# lvc.net
KiCad netlist of a schematic drawn in EAGLE
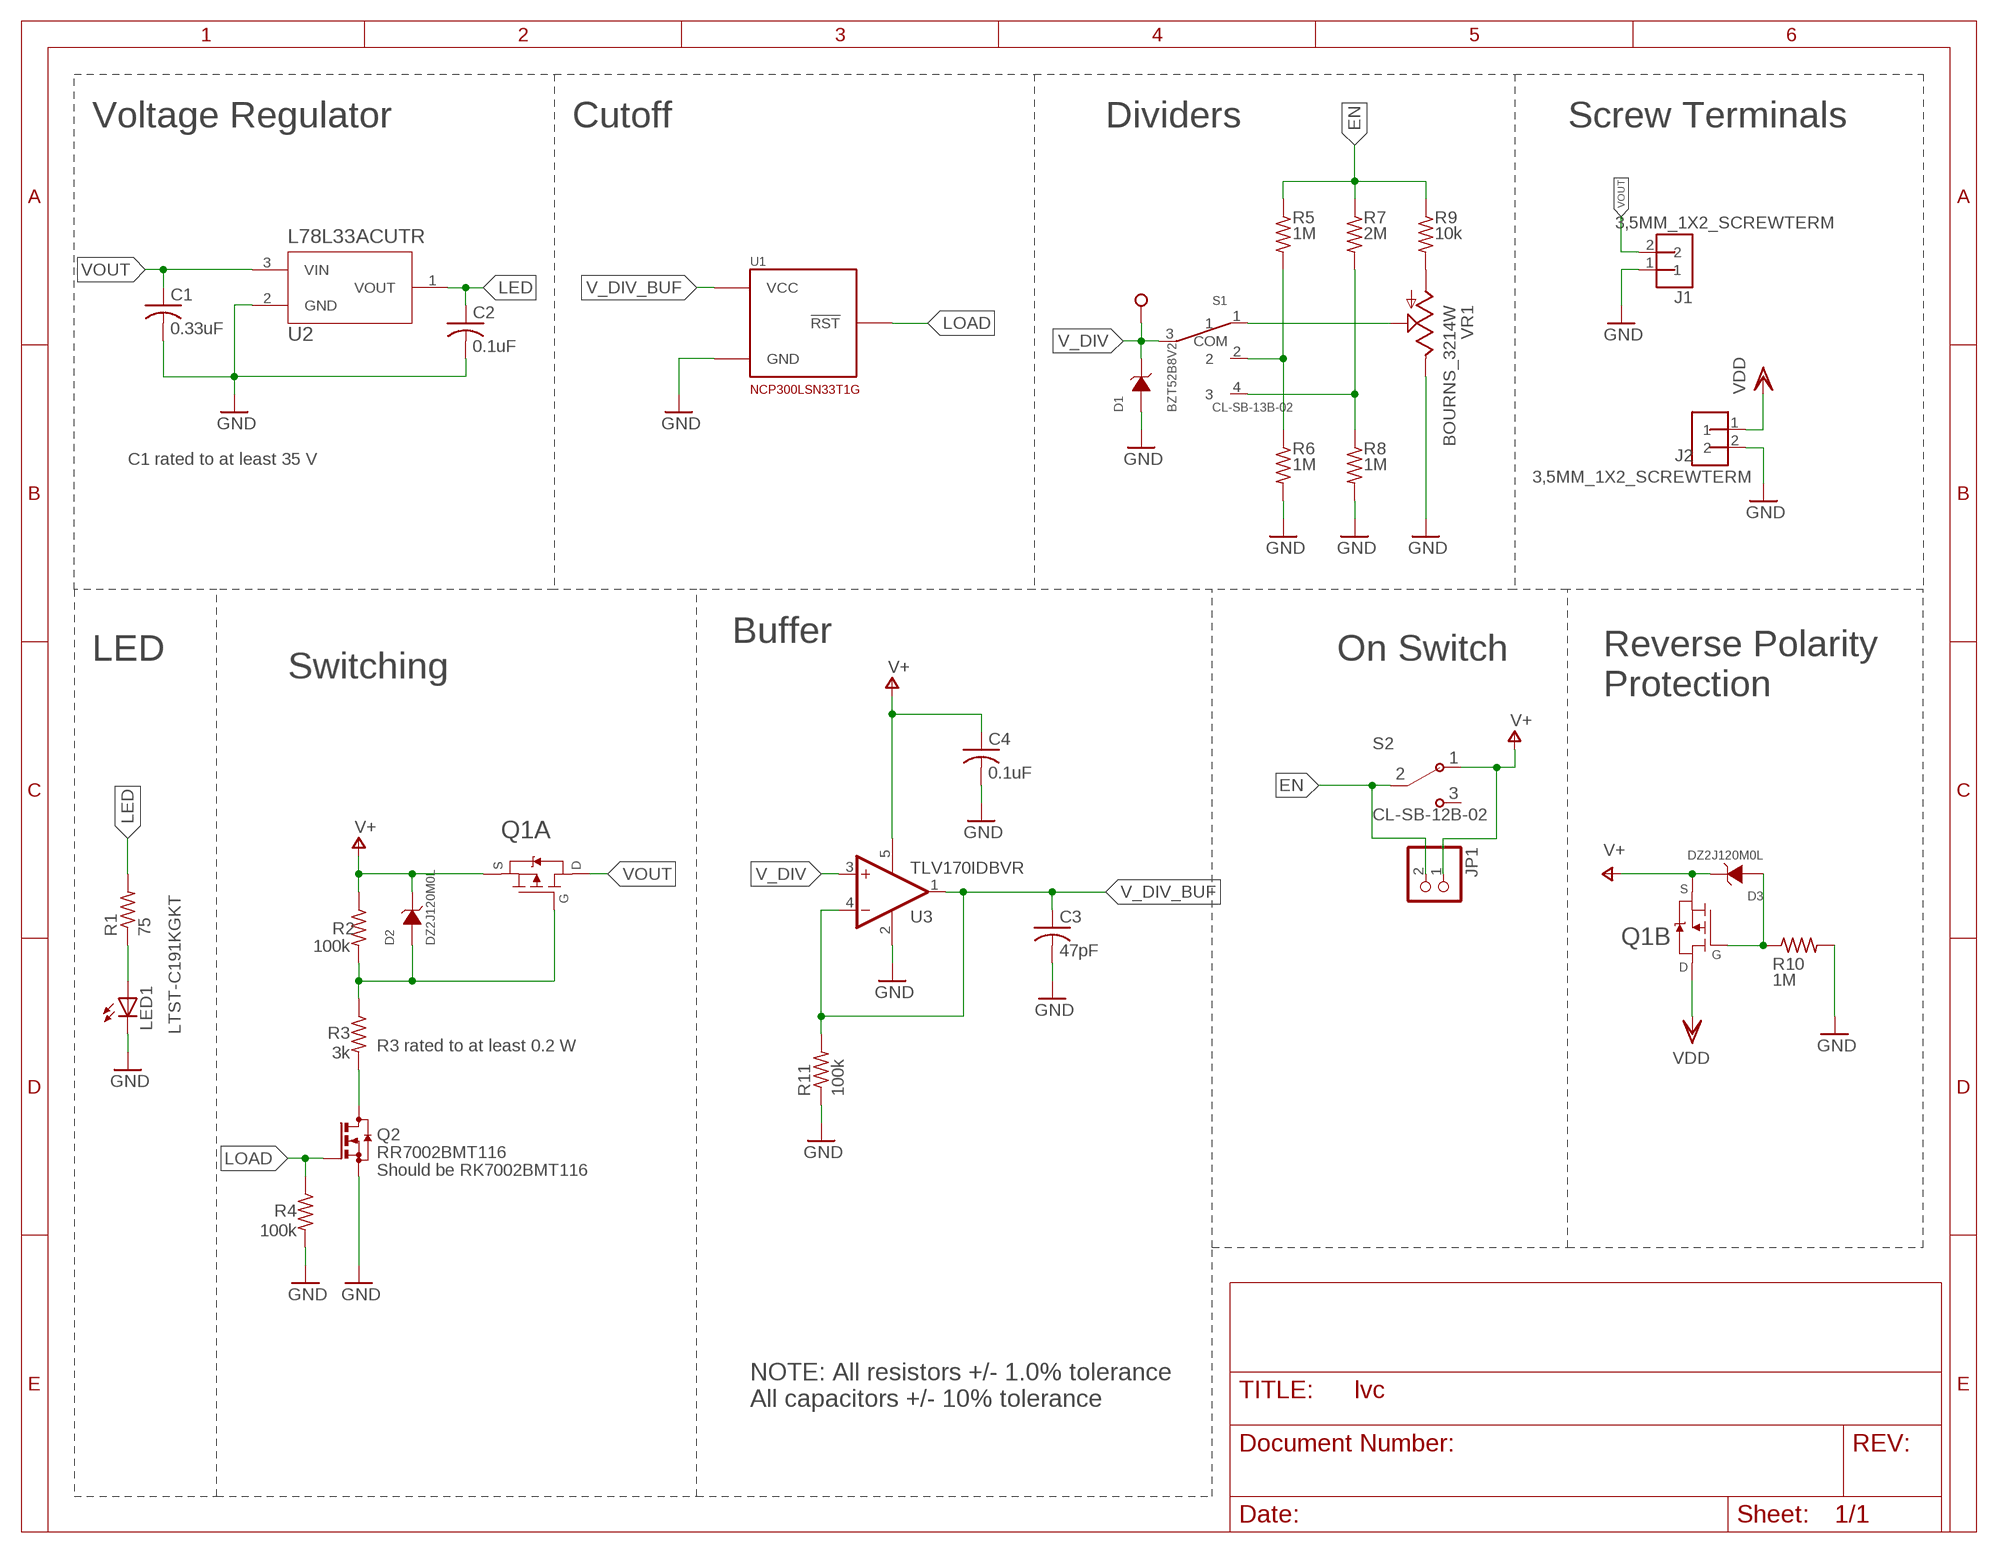
[diagram p0: schematic, sheet 1]

(export (version "E")
  (design (tool "Eeschema 10.0.6"))
  (components
    (comp (ref "C1")
      (value "0.33uF")
      (footprint "eagle-import:C0603")
      (libsource (lib "eagle-import") (part "C-USC0603"))
    )
    (comp (ref "C2")
      (value "0.1uF")
      (footprint "eagle-import:C0603")
      (libsource (lib "eagle-import") (part "C-USC0603"))
    )
    (comp (ref "C3")
      (value "47pF")
      (footprint "eagle-import:C0603")
      (libsource (lib "eagle-import") (part "C-USC0603"))
    )
    (comp (ref "C4")
      (value "0.1uF")
      (footprint "eagle-import:C0603")
      (libsource (lib "eagle-import") (part "C-USC0603"))
    )
    (comp (ref "D1")
      (value "BZT52B8V2")
      (footprint "eagle-import:SOD123")
      (libsource (lib "eagle-import") (part "BZT52B8V2"))
    )
    (comp (ref "D2")
      (value "DZ2J120M0L")
      (footprint "eagle-import:SMINI2-F5-B")
      (libsource (lib "eagle-import") (part "DZ2J120M0L"))
    )
    (comp (ref "D3")
      (value "DZ2J120M0L")
      (footprint "eagle-import:SMINI2-F5-B")
      (libsource (lib "eagle-import") (part "DZ2J120M0L"))
    )
    (comp (ref "J1")
      (value "3,5MM_1X2_SCREWTERM")
      (footprint "eagle-import:3.5MM_1X2")
      (libsource (lib "eagle-import") (part "3,5MM_1X2_SCREWTERM"))
    )
    (comp (ref "J2")
      (value "3,5MM_1X2_SCREWTERM")
      (footprint "eagle-import:3.5MM_1X2")
      (libsource (lib "eagle-import") (part "3,5MM_1X2_SCREWTERM"))
    )
    (comp (ref "JP1")
      (value "PINHD-1X2")
      (footprint "eagle-import:1X02")
      (libsource (lib "eagle-import") (part "PINHD-1X2"))
    )
    (comp (ref "LED1")
      (value "LEDCHIPLED_0603")
      (footprint "eagle-import:CHIPLED_0603")
      (libsource (lib "eagle-import") (part "LEDCHIPLED_0603"))
    )
    (comp (ref "Q1")
      (value "SI7997DP")
      (footprint "eagle-import:POWERPAK-SO-8-DUAL")
      (libsource (lib "eagle-import") (part "SI7997DP"))
    )
    (comp (ref "Q2")
      (value "RR7002BMT116")
      (footprint "eagle-import:SOT23")
      (libsource (lib "eagle-import") (part "RR7002BMT116"))
    )
    (comp (ref "R1")
      (value "75")
      (footprint "eagle-import:R0603")
      (libsource (lib "eagle-import") (part "R-US_R0603"))
    )
    (comp (ref "R2")
      (value "100k")
      (footprint "eagle-import:R0603")
      (libsource (lib "eagle-import") (part "resistor_348_R-US_R0603"))
    )
    (comp (ref "R3")
      (value "3k")
      (footprint "eagle-import:R0603")
      (libsource (lib "eagle-import") (part "resistor_348_R-US_R0603"))
    )
    (comp (ref "R4")
      (value "100k")
      (footprint "eagle-import:R0603")
      (libsource (lib "eagle-import") (part "resistor_348_R-US_R0603"))
    )
    (comp (ref "R5")
      (value "1M")
      (footprint "eagle-import:R0603")
      (libsource (lib "eagle-import") (part "resistor_348_R-US_R0603"))
    )
    (comp (ref "R6")
      (value "1M")
      (footprint "eagle-import:R0603")
      (libsource (lib "eagle-import") (part "resistor_348_R-US_R0603"))
    )
    (comp (ref "R7")
      (value "2M")
      (footprint "eagle-import:R0603")
      (libsource (lib "eagle-import") (part "resistor_348_R-US_R0603"))
    )
    (comp (ref "R8")
      (value "1M")
      (footprint "eagle-import:R0603")
      (libsource (lib "eagle-import") (part "resistor_348_R-US_R0603"))
    )
    (comp (ref "R9")
      (value "10k")
      (footprint "eagle-import:R0603")
      (libsource (lib "eagle-import") (part "resistor_348_R-US_R0603"))
    )
    (comp (ref "R10")
      (value "1M")
      (footprint "eagle-import:R0603")
      (libsource (lib "eagle-import") (part "resistor_348_R-US_R0603"))
    )
    (comp (ref "R11")
      (value "100k")
      (footprint "eagle-import:R0603")
      (libsource (lib "eagle-import") (part "R-US_R0603"))
    )
    (comp (ref "S1")
      (value "CL-SB-13B-02")
      (footprint "eagle-import:CL-SB-13B")
      (libsource (lib "eagle-import") (part "CL-SB-13B-02"))
    )
    (comp (ref "S2")
      (value "CL-SB-12B-02")
      (footprint "eagle-import:CL-SB-12B")
      (libsource (lib "eagle-import") (part "CL-SB-12B-02"))
    )
    (comp (ref "TP2")
      (value "TESTPOINTNOCREAM")
      (footprint "eagle-import:TP_2.5MM_NOCREAM")
      (libsource (lib "eagle-import") (part "TESTPOINTNOCREAM"))
    )
    (comp (ref "U1")
      (value "NCP300LSN33T1G")
      (footprint "eagle-import:SOT23-5")
      (libsource (lib "eagle-import") (part "NCP300LSN33T1G"))
    )
    (comp (ref "U2")
      (value "L78L33ACUTR")
      (footprint "eagle-import:SOT-89")
      (libsource (lib "eagle-import") (part "L78L33ACUTR"))
    )
    (comp (ref "U3")
      (value "TLV170IDBVR")
      (footprint "eagle-import:SOT23-DBV")
      (libsource (lib "eagle-import") (part "TLV170IDBVR"))
    )
    (comp (ref "VR1")
      (value "BOURNS_3214W")
      (footprint "eagle-import:J-LEAD_TOP_ADJ")
      (libsource (lib "eagle-import") (part "BOURNS_3214W"))
    )
  )
  (nets
    (net (code "1") (name "EN") (class "Default")
      (node (ref "JP1") (pin "2") (pinfunction "2_2") (pintype "passive"))
      (node (ref "R5") (pin "1") (pinfunction "1_1") (pintype "passive"))
      (node (ref "R7") (pin "1") (pinfunction "1_1") (pintype "passive"))
      (node (ref "R9") (pin "1") (pinfunction "1_1") (pintype "passive"))
      (node (ref "S2") (pin "1") (pinfunction "P$1_1") (pintype "bidirectional"))
    )
    (net (code "2") (name "GND") (class "Default")
      (node (ref "C1") (pin "2") (pinfunction "2_2") (pintype "passive"))
      (node (ref "C2") (pin "2") (pinfunction "2_2") (pintype "passive"))
      (node (ref "C3") (pin "2") (pinfunction "2_2") (pintype "passive"))
      (node (ref "C4") (pin "2") (pinfunction "2_2") (pintype "passive"))
      (node (ref "D1") (pin "A") (pinfunction "A_A") (pintype "bidirectional"))
      (node (ref "J1") (pin "1") (pinfunction "1_1") (pintype "bidirectional"))
      (node (ref "J2") (pin "2") (pinfunction "2_2") (pintype "bidirectional"))
      (node (ref "LED1") (pin "C") (pinfunction "C_C") (pintype "passive"))
      (node (ref "Q2") (pin "2") (pinfunction "S_2") (pintype "passive"))
      (node (ref "R10") (pin "2") (pinfunction "2_2") (pintype "passive"))
      (node (ref "R11") (pin "1") (pinfunction "1_1") (pintype "passive"))
      (node (ref "R4") (pin "2") (pinfunction "2_2") (pintype "passive"))
      (node (ref "R6") (pin "2") (pinfunction "2_2") (pintype "passive"))
      (node (ref "R8") (pin "2") (pinfunction "2_2") (pintype "passive"))
      (node (ref "U1") (pin "3") (pinfunction "GND_3") (pintype "power_in"))
      (node (ref "U2") (pin "2") (pinfunction "GND_2") (pintype "passive"))
      (node (ref "U3") (pin "2") (pinfunction "V-_2") (pintype "power_in"))
      (node (ref "VR1") (pin "3") (pinfunction "E_3") (pintype "passive"))
    )
    (net (code "3") (name "LED") (class "Default")
      (node (ref "C2") (pin "1") (pinfunction "1_1") (pintype "passive"))
      (node (ref "R1") (pin "2") (pinfunction "2_2") (pintype "passive"))
      (node (ref "U2") (pin "1") (pinfunction "VOUT_1") (pintype "output"))
    )
    (net (code "4") (name "LOAD") (class "Default")
      (node (ref "Q2") (pin "1") (pinfunction "G_1") (pintype "passive"))
      (node (ref "R4") (pin "1") (pinfunction "1_1") (pintype "passive"))
      (node (ref "U1") (pin "1") (pinfunction "~{RST}_1") (pintype "bidirectional"))
    )
    (net (code "5") (name "Net-(LED1-PadA)") (class "Default")
      (node (ref "LED1") (pin "A") (pinfunction "A_A") (pintype "passive"))
      (node (ref "R1") (pin "1") (pinfunction "1_1") (pintype "passive"))
    )
    (net (code "6") (name "Net-(Q1A-G)") (class "Default")
      (node (ref "D2") (pin "A") (pinfunction "A_A") (pintype "passive"))
      (node (ref "Q1") (pin "4") (pinfunction "G_4") (pintype "bidirectional"))
      (node (ref "R2") (pin "2") (pinfunction "2_2") (pintype "passive"))
      (node (ref "R3") (pin "1") (pinfunction "1_1") (pintype "passive"))
    )
    (net (code "7") (name "Net-(Q1B-G)") (class "Default")
      (node (ref "D3") (pin "A") (pinfunction "A_A") (pintype "passive"))
      (node (ref "Q1") (pin "2") (pinfunction "G_2") (pintype "bidirectional"))
      (node (ref "R10") (pin "1") (pinfunction "1_1") (pintype "passive"))
    )
    (net (code "8") (name "Net-(Q2-D)") (class "Default")
      (node (ref "Q2") (pin "3") (pinfunction "D_3") (pintype "passive"))
      (node (ref "R3") (pin "2") (pinfunction "2_2") (pintype "passive"))
    )
    (net (code "9") (name "Net-(R5-Pad2)") (class "Default")
      (node (ref "R5") (pin "2") (pinfunction "2_2") (pintype "passive"))
      (node (ref "R6") (pin "1") (pinfunction "1_1") (pintype "passive"))
      (node (ref "S1") (pin "2") (pinfunction "2_2") (pintype "bidirectional"))
    )
    (net (code "10") (name "Net-(S1-3)") (class "Default")
      (node (ref "R7") (pin "2") (pinfunction "2_2") (pintype "passive"))
      (node (ref "R8") (pin "1") (pinfunction "1_1") (pintype "passive"))
      (node (ref "S1") (pin "4") (pinfunction "3_4") (pintype "bidirectional"))
    )
    (net (code "11") (name "Net-(VR1-A)") (class "Default")
      (node (ref "R9") (pin "2") (pinfunction "2_2") (pintype "passive"))
      (node (ref "VR1") (pin "1") (pinfunction "A_1") (pintype "passive"))
    )
    (net (code "12") (name "Net-(VR1-S)") (class "Default")
      (node (ref "S1") (pin "1") (pinfunction "1_1") (pintype "bidirectional"))
      (node (ref "VR1") (pin "2") (pinfunction "S_2") (pintype "passive"))
    )
    (net (code "13") (name "V+") (class "Default")
      (node (ref "C4") (pin "1") (pinfunction "1_1") (pintype "passive"))
      (node (ref "D2") (pin "C") (pinfunction "C_C") (pintype "passive"))
      (node (ref "D3") (pin "C") (pinfunction "C_C") (pintype "passive"))
      (node (ref "JP1") (pin "1") (pinfunction "1_1") (pintype "passive"))
      (node (ref "Q1") (pin "1") (pinfunction "S_1") (pintype "bidirectional"))
      (node (ref "Q1") (pin "3") (pinfunction "S_3") (pintype "bidirectional"))
      (node (ref "R2") (pin "1") (pinfunction "1_1") (pintype "passive"))
      (node (ref "S2") (pin "2") (pinfunction "P$2_2") (pintype "bidirectional"))
      (node (ref "U3") (pin "5") (pinfunction "V+_5") (pintype "power_in"))
    )
    (net (code "14") (name "VDD") (class "Default")
      (node (ref "J2") (pin "1") (pinfunction "1_1") (pintype "bidirectional"))
      (node (ref "Q1") (pin "7") (pinfunction "D_7") (pintype "bidirectional"))
      (node (ref "Q1") (pin "8") (pinfunction "D_8") (pintype "bidirectional"))
      (node (ref "Q1") (pin "8L") (pinfunction "D_8L") (pintype "bidirectional"))
    )
    (net (code "15") (name "VOUT") (class "Default")
      (node (ref "C1") (pin "1") (pinfunction "1_1") (pintype "passive"))
      (node (ref "J1") (pin "2") (pinfunction "2_2") (pintype "bidirectional"))
      (node (ref "Q1") (pin "5") (pinfunction "D_5") (pintype "bidirectional"))
      (node (ref "Q1") (pin "5L") (pinfunction "D_5L") (pintype "bidirectional"))
      (node (ref "Q1") (pin "6") (pinfunction "D_6") (pintype "bidirectional"))
      (node (ref "U2") (pin "3") (pinfunction "VIN_3") (pintype "input"))
    )
    (net (code "16") (name "V_DIV") (class "Default")
      (node (ref "D1") (pin "C") (pinfunction "C_C") (pintype "bidirectional"))
      (node (ref "S1") (pin "3") (pinfunction "COM_3") (pintype "bidirectional"))
      (node (ref "TP2") (pin "P$1") (pinfunction "P$1_P$1") (pintype "bidirectional"))
      (node (ref "U3") (pin "3") (pinfunction "+IN_3") (pintype "input"))
    )
    (net (code "17") (name "V_DIV_BUF") (class "Default")
      (node (ref "C3") (pin "1") (pinfunction "1_1") (pintype "passive"))
      (node (ref "R11") (pin "2") (pinfunction "2_2") (pintype "passive"))
      (node (ref "U1") (pin "2") (pinfunction "VCC_2") (pintype "power_in"))
      (node (ref "U3") (pin "1") (pinfunction "OUT_1") (pintype "output"))
      (node (ref "U3") (pin "4") (pinfunction "-IN_4") (pintype "input"))
    )
    (net (code "18") (name "unconnected-(S2-P$3-Pad3)") (class "Default")
      (node (ref "S2") (pin "3") (pinfunction "P$3_3") (pintype "bidirectional"))
    )
  )
)
